# untitled.net
KiCad netlist of a schematic drawn in EAGLE
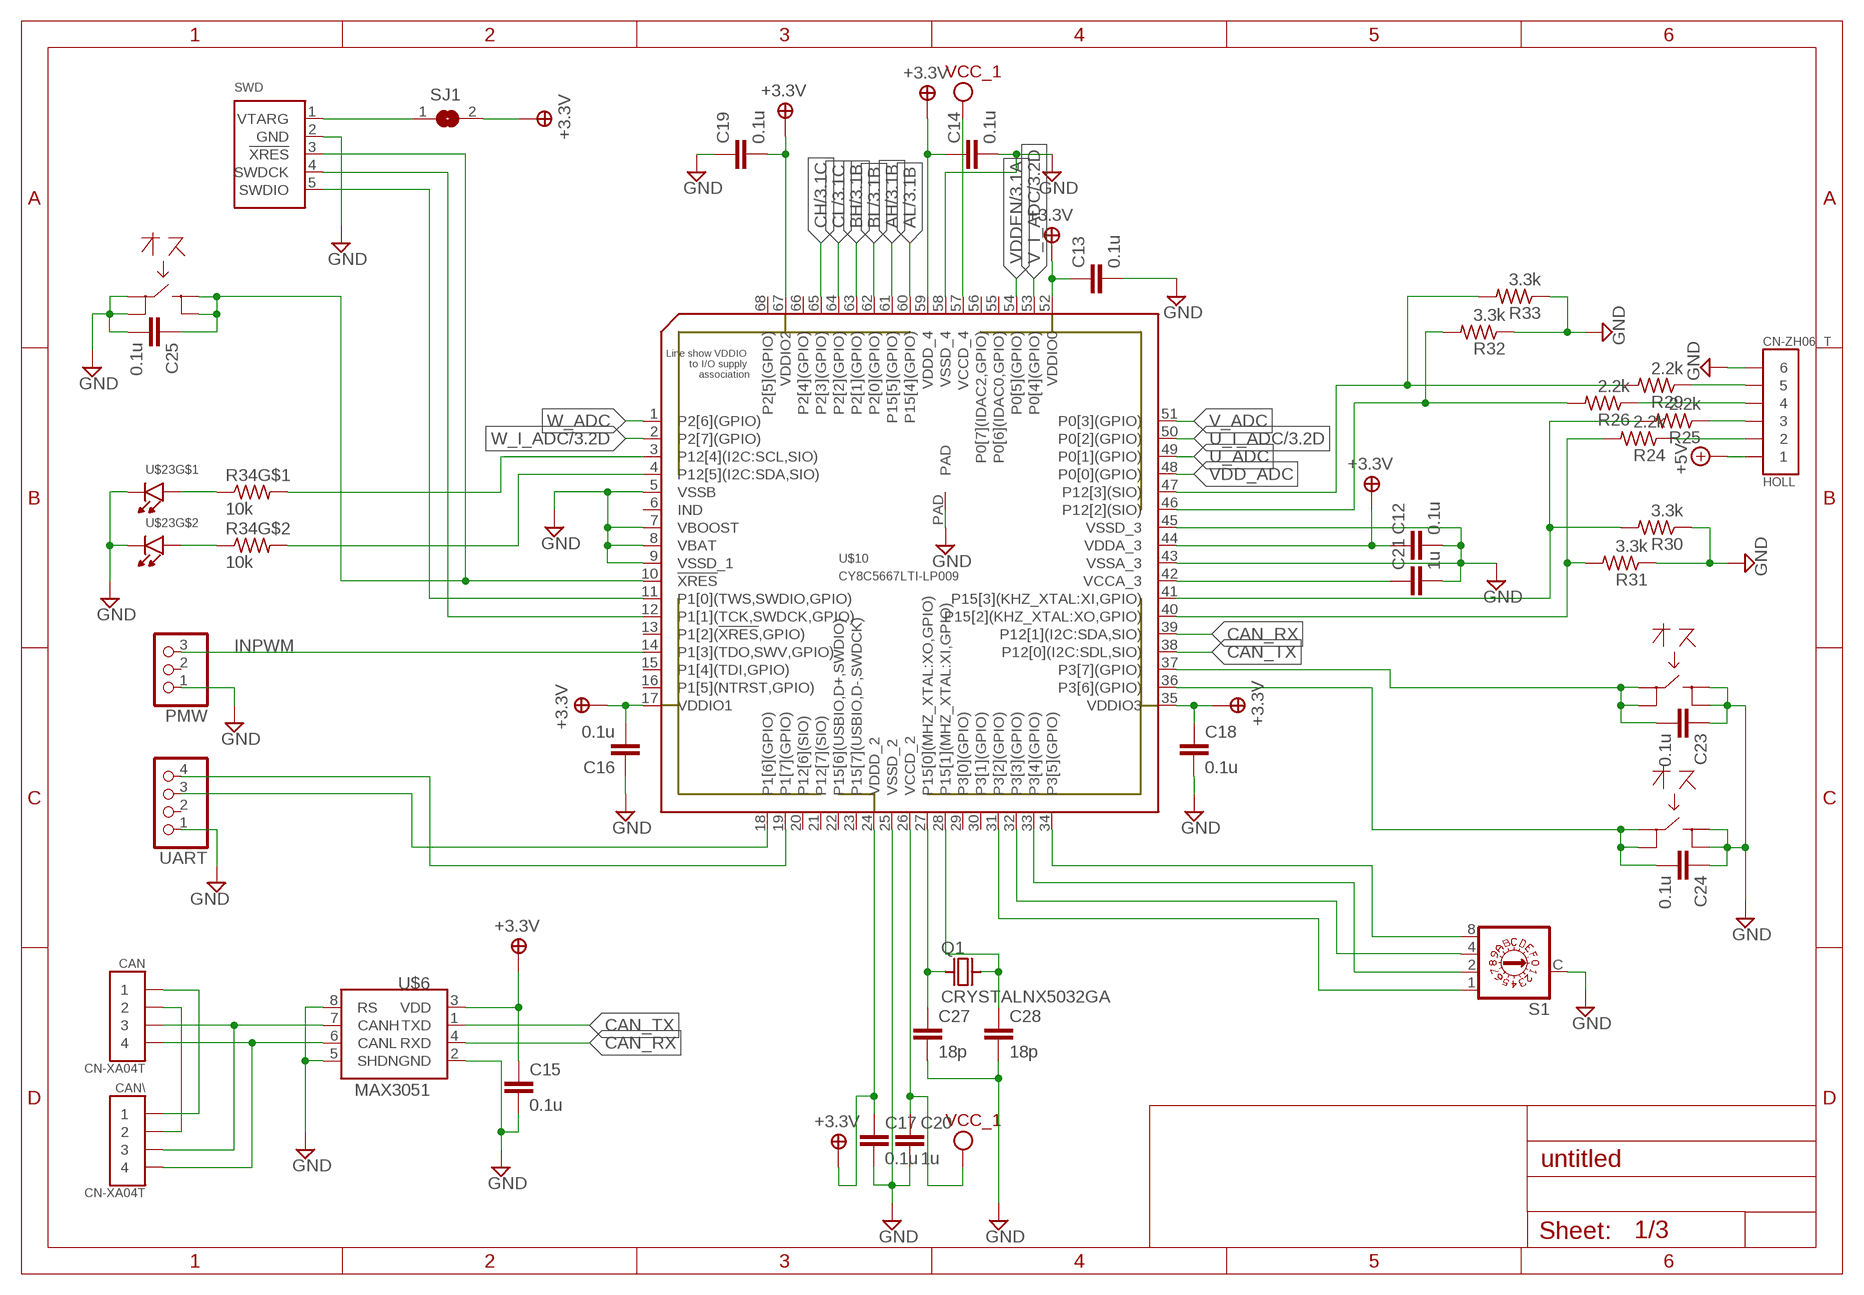
[diagram p0: schematic, sheet 1]
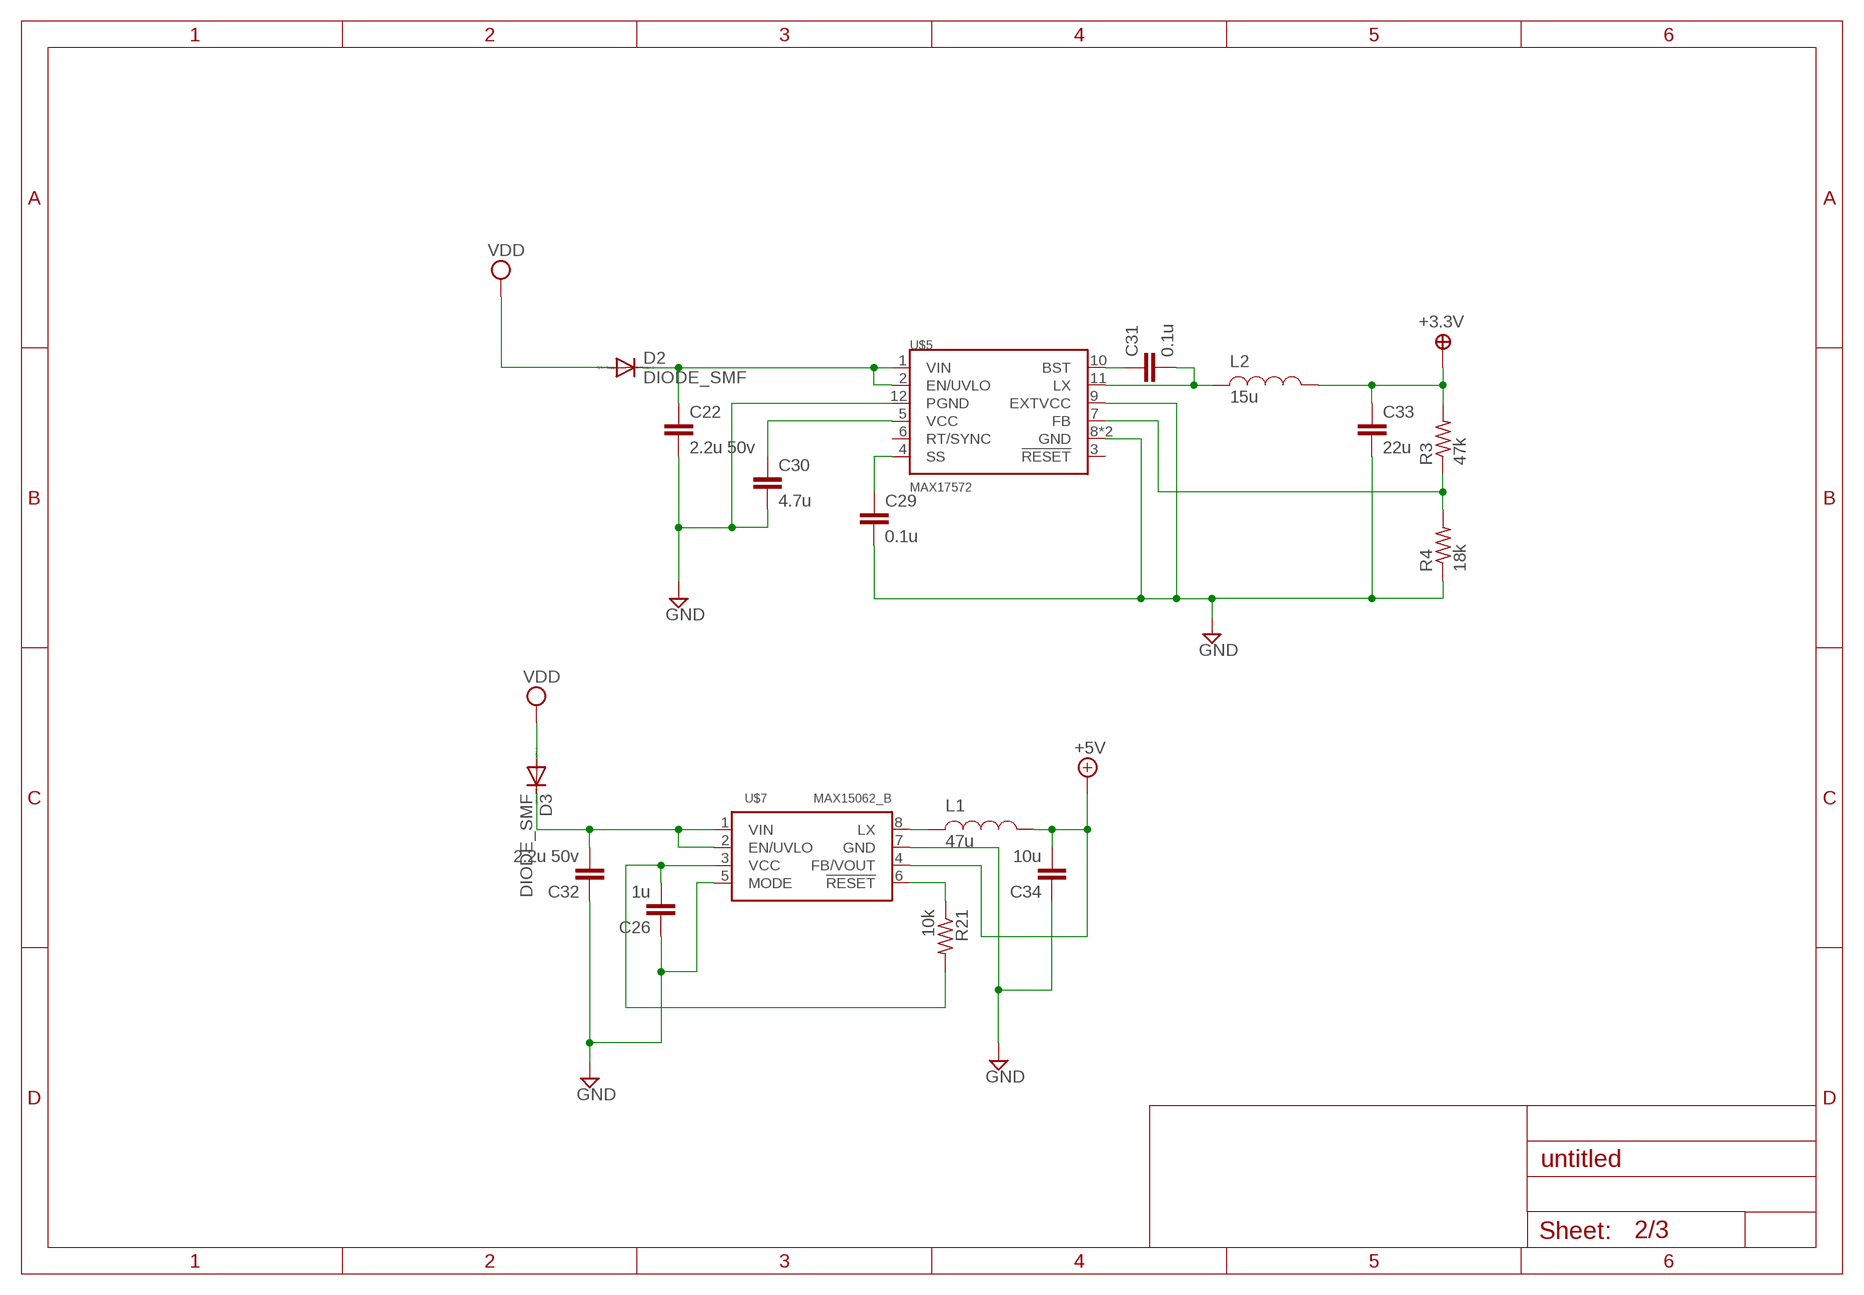
[diagram p1: schematic, sheet 2]
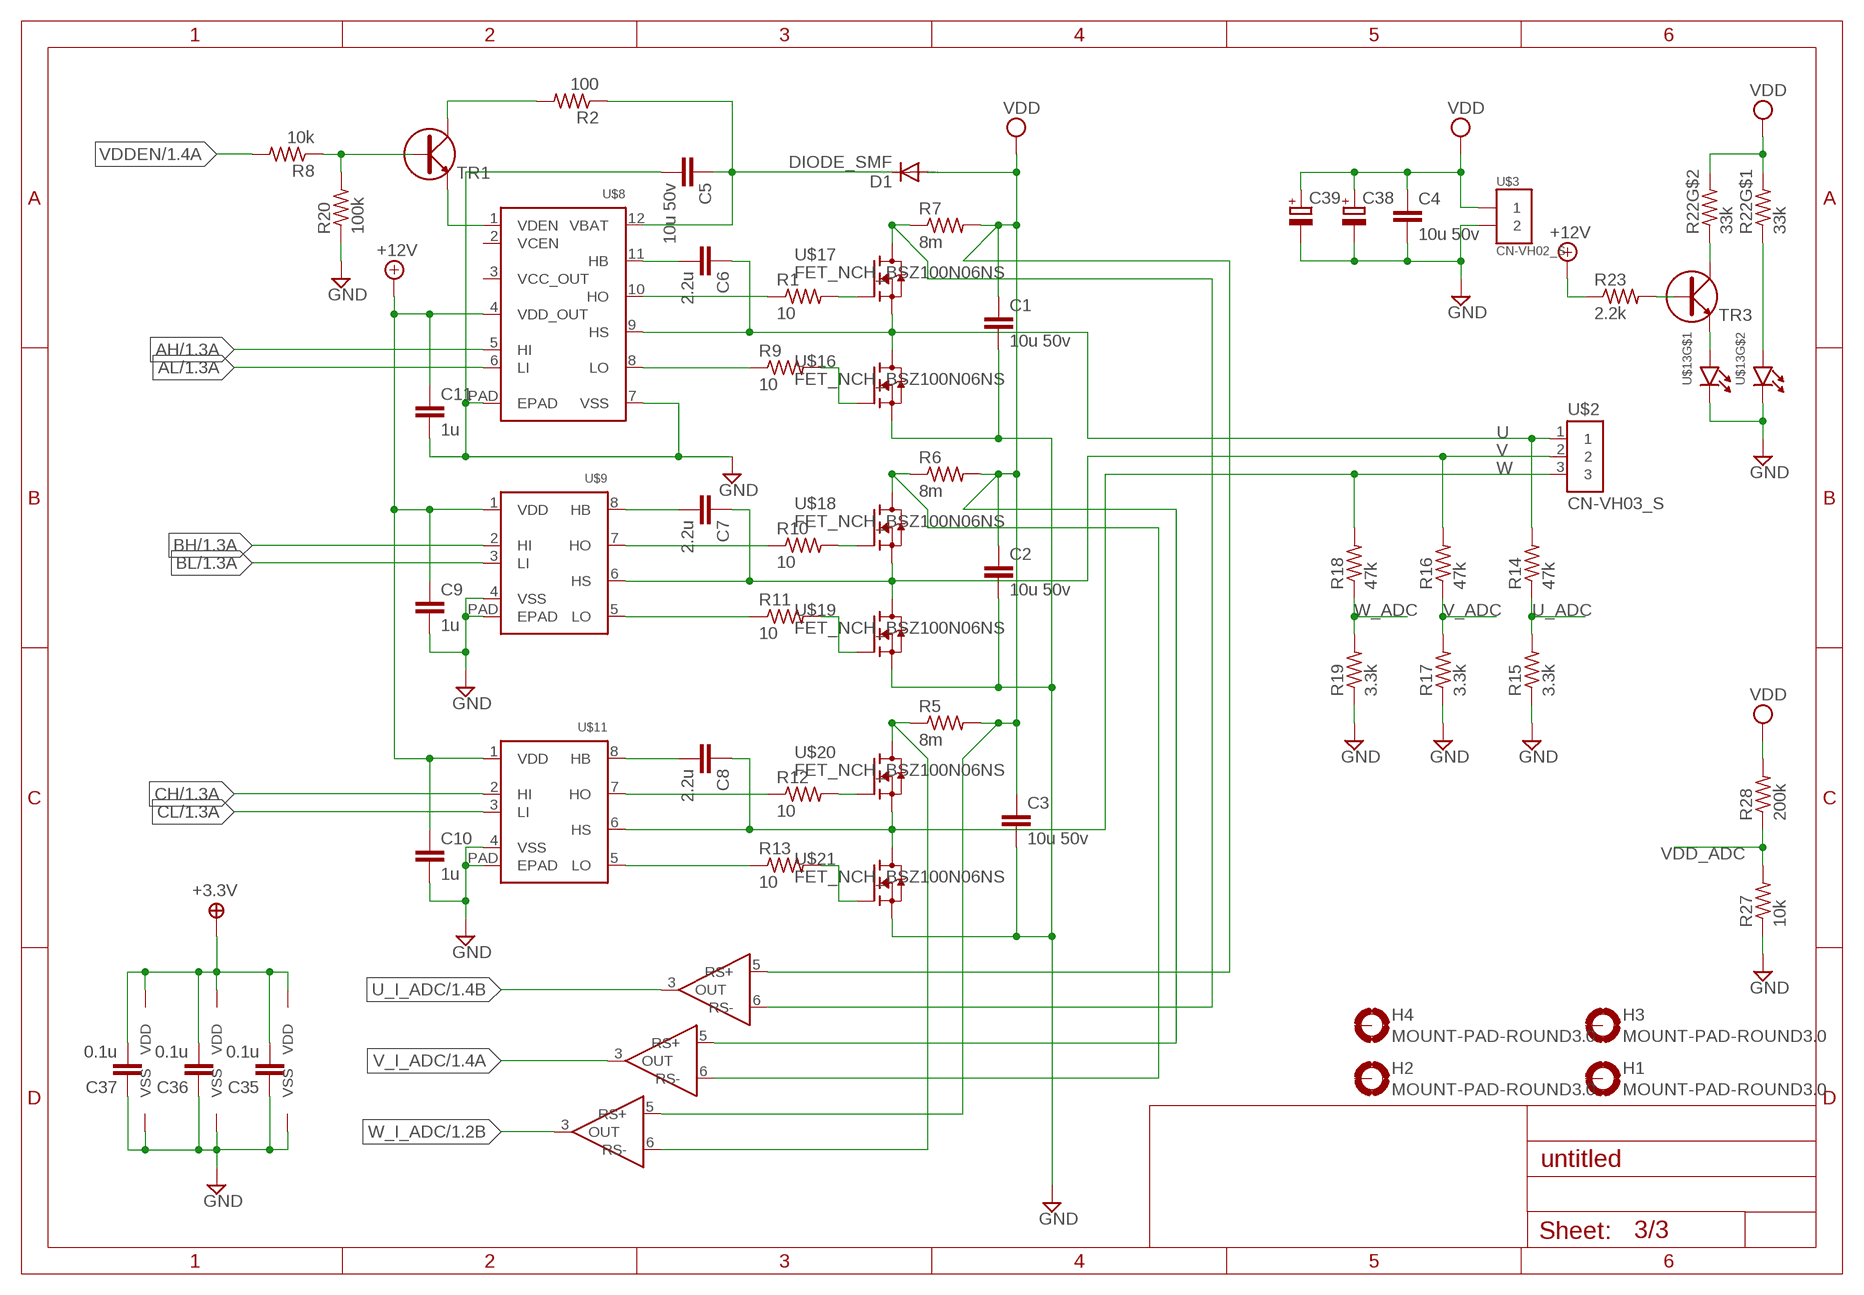
[diagram p2: schematic, sheet 3]

(export (version "E")
  (design (tool "Eeschema 10.0.6"))
  (components
    (comp (ref "C1")
      (value "10u 50v")
      (footprint "eagle-import:C3216")
      (libsource (lib "eagle-import") (part "CAPACITOR_3216M"))
    )
    (comp (ref "C2")
      (value "10u 50v")
      (footprint "eagle-import:C3216")
      (libsource (lib "eagle-import") (part "CAPACITOR_3216M"))
    )
    (comp (ref "C3")
      (value "10u 50v")
      (footprint "eagle-import:C3216")
      (libsource (lib "eagle-import") (part "CAPACITOR_3216M"))
    )
    (comp (ref "C4")
      (value "10u 50v")
      (footprint "eagle-import:C3216")
      (libsource (lib "eagle-import") (part "CAPACITOR_3216M"))
    )
    (comp (ref "C5")
      (value "10u 50v")
      (footprint "eagle-import:C3216")
      (libsource (lib "eagle-import") (part "CAPACITOR_3216M"))
    )
    (comp (ref "C6")
      (value "2.2u")
      (footprint "eagle-import:C1005")
      (libsource (lib "eagle-import") (part "CAPACITOR_1005M"))
    )
    (comp (ref "C7")
      (value "2.2u")
      (footprint "eagle-import:C1005")
      (libsource (lib "eagle-import") (part "CAPACITOR_1005M"))
    )
    (comp (ref "C8")
      (value "2.2u")
      (footprint "eagle-import:C1005")
      (libsource (lib "eagle-import") (part "CAPACITOR_1005M"))
    )
    (comp (ref "C9")
      (value "1u")
      (footprint "eagle-import:C1608")
      (libsource (lib "eagle-import") (part "CAPACITOR_1608M"))
    )
    (comp (ref "C10")
      (value "1u")
      (footprint "eagle-import:C1608")
      (libsource (lib "eagle-import") (part "CAPACITOR_1608M"))
    )
    (comp (ref "C11")
      (value "1u")
      (footprint "eagle-import:C1608")
      (libsource (lib "eagle-import") (part "CAPACITOR_1608M"))
    )
    (comp (ref "C35")
      (value "0.1u")
      (footprint "eagle-import:C1005")
      (libsource (lib "eagle-import") (part "CAPACITOR_1005M"))
    )
    (comp (ref "C36")
      (value "0.1u")
      (footprint "eagle-import:C1005")
      (libsource (lib "eagle-import") (part "CAPACITOR_1005M"))
    )
    (comp (ref "C37")
      (value "0.1u")
      (footprint "eagle-import:C1005")
      (libsource (lib "eagle-import") (part "CAPACITOR_1005M"))
    )
    (comp (ref "C38")
      (value "CPOL-EUG")
      (footprint "eagle-import:PANASONIC_G")
      (libsource (lib "eagle-import") (part "CPOL-EUG"))
    )
    (comp (ref "C39")
      (value "CPOL-EUE5-13")
      (footprint "eagle-import:E5-13")
      (libsource (lib "eagle-import") (part "CPOL-EUE5-13"))
    )
    (comp (ref "D1")
      (value "DIODE_SMF")
      (footprint "eagle-import:DO-219AB(SMF)")
      (libsource (lib "eagle-import") (part "DIODE_SMF"))
    )
    (comp (ref "H1")
      (value "MOUNT-PAD-ROUND3.0")
      (footprint "eagle-import:3,0-PAD")
      (libsource (lib "eagle-import") (part "MOUNT-PAD-ROUND3.0"))
    )
    (comp (ref "H2")
      (value "MOUNT-PAD-ROUND3.0")
      (footprint "eagle-import:3,0-PAD")
      (libsource (lib "eagle-import") (part "MOUNT-PAD-ROUND3.0"))
    )
    (comp (ref "H3")
      (value "MOUNT-PAD-ROUND3.0")
      (footprint "eagle-import:3,0-PAD")
      (libsource (lib "eagle-import") (part "MOUNT-PAD-ROUND3.0"))
    )
    (comp (ref "H4")
      (value "MOUNT-PAD-ROUND3.0")
      (footprint "eagle-import:3,0-PAD")
      (libsource (lib "eagle-import") (part "MOUNT-PAD-ROUND3.0"))
    )
    (comp (ref "R1")
      (value "10")
      (footprint "eagle-import:R1608")
      (libsource (lib "eagle-import") (part "R_1608"))
    )
    (comp (ref "R2")
      (value "100")
      (footprint "eagle-import:R1005")
      (libsource (lib "eagle-import") (part "R_1005"))
    )
    (comp (ref "R5")
      (value "8m")
      (footprint "eagle-import:R3216")
      (libsource (lib "eagle-import") (part "R_3216"))
    )
    (comp (ref "R6")
      (value "8m")
      (footprint "eagle-import:R3216")
      (libsource (lib "eagle-import") (part "R_3216"))
    )
    (comp (ref "R7")
      (value "8m")
      (footprint "eagle-import:R3216")
      (libsource (lib "eagle-import") (part "R_3216"))
    )
    (comp (ref "R8")
      (value "10k")
      (footprint "eagle-import:R1005")
      (libsource (lib "eagle-import") (part "R_1005"))
    )
    (comp (ref "R9")
      (value "10")
      (footprint "eagle-import:R1608")
      (libsource (lib "eagle-import") (part "R_1608"))
    )
    (comp (ref "R10")
      (value "10")
      (footprint "eagle-import:R1608")
      (libsource (lib "eagle-import") (part "R_1608"))
    )
    (comp (ref "R11")
      (value "10")
      (footprint "eagle-import:R1608")
      (libsource (lib "eagle-import") (part "R_1608"))
    )
    (comp (ref "R12")
      (value "10")
      (footprint "eagle-import:R1608")
      (libsource (lib "eagle-import") (part "R_1608"))
    )
    (comp (ref "R13")
      (value "10")
      (footprint "eagle-import:R1608")
      (libsource (lib "eagle-import") (part "R_1608"))
    )
    (comp (ref "R14")
      (value "47k")
      (footprint "eagle-import:R1005")
      (libsource (lib "eagle-import") (part "R_1005"))
    )
    (comp (ref "R15")
      (value "3.3k")
      (footprint "eagle-import:R1005")
      (libsource (lib "eagle-import") (part "R_1005"))
    )
    (comp (ref "R16")
      (value "47k")
      (footprint "eagle-import:R1005")
      (libsource (lib "eagle-import") (part "R_1005"))
    )
    (comp (ref "R17")
      (value "3.3k")
      (footprint "eagle-import:R1005")
      (libsource (lib "eagle-import") (part "R_1005"))
    )
    (comp (ref "R18")
      (value "47k")
      (footprint "eagle-import:R1005")
      (libsource (lib "eagle-import") (part "R_1005"))
    )
    (comp (ref "R19")
      (value "3.3k")
      (footprint "eagle-import:R1005")
      (libsource (lib "eagle-import") (part "R_1005"))
    )
    (comp (ref "R20")
      (value "100k")
      (footprint "eagle-import:R1005")
      (libsource (lib "eagle-import") (part "R_1005"))
    )
    (comp (ref "R22")
      (value "33k")
      (footprint "eagle-import:R1005_2")
      (libsource (lib "eagle-import") (part "R2_0402"))
    )
    (comp (ref "R23")
      (value "2.2k")
      (footprint "eagle-import:R1005")
      (libsource (lib "eagle-import") (part "R_1005"))
    )
    (comp (ref "R27")
      (value "10k")
      (footprint "eagle-import:R1005")
      (libsource (lib "eagle-import") (part "R_1005"))
    )
    (comp (ref "R28")
      (value "200k")
      (footprint "eagle-import:R1005")
      (libsource (lib "eagle-import") (part "R_1005"))
    )
    (comp (ref "TR1")
      (value "TR_NTR")
      (footprint "eagle-import:SOT-23-3")
      (libsource (lib "eagle-import") (part "TR_NTR"))
    )
    (comp (ref "TR3")
      (value "TR_NTR")
      (footprint "eagle-import:SOT-23-3")
      (libsource (lib "eagle-import") (part "TR_NTR"))
    )
    (comp (ref "U$2")
      (value "CN-VH03_S")
      (footprint "eagle-import:VH03-S")
      (libsource (lib "eagle-import") (part "CN-VH03_S"))
    )
    (comp (ref "U$3")
      (value "CN-VH02_S")
      (footprint "eagle-import:VH02-S")
      (libsource (lib "eagle-import") (part "CN-VH02_S"))
    )
    (comp (ref "U$8")
      (value "HIP2104")
      (footprint "eagle-import:DFN_4X4_12LD")
      (libsource (lib "eagle-import") (part "HIP2104"))
    )
    (comp (ref "U$9")
      (value "HIP2103")
      (footprint "eagle-import:DFN_3X3_8L")
      (libsource (lib "eagle-import") (part "HIP2103"))
    )
    (comp (ref "U$11")
      (value "HIP2103")
      (footprint "eagle-import:DFN_3X3_8L")
      (libsource (lib "eagle-import") (part "HIP2103"))
    )
    (comp (ref "U$13")
      (value "LED2_SML522")
      (footprint "eagle-import:LED1315")
      (libsource (lib "eagle-import") (part "LED2_SML522"))
    )
    (comp (ref "U$14")
      (value "MAX40010")
      (footprint "eagle-import:SOT-23-6")
      (libsource (lib "eagle-import") (part "MAX40010"))
    )
    (comp (ref "U$15")
      (value "MAX40010")
      (footprint "eagle-import:SOT-23-6")
      (libsource (lib "eagle-import") (part "MAX40010"))
    )
    (comp (ref "U$16")
      (value "FET_NCH_BSZ100N06NS")
      (footprint "eagle-import:TSDSON-8")
      (libsource (lib "eagle-import") (part "FET_NCH_BSZ100N06NS"))
    )
    (comp (ref "U$17")
      (value "FET_NCH_BSZ100N06NS")
      (footprint "eagle-import:TSDSON-8")
      (libsource (lib "eagle-import") (part "FET_NCH_BSZ100N06NS"))
    )
    (comp (ref "U$18")
      (value "FET_NCH_BSZ100N06NS")
      (footprint "eagle-import:TSDSON-8")
      (libsource (lib "eagle-import") (part "FET_NCH_BSZ100N06NS"))
    )
    (comp (ref "U$19")
      (value "FET_NCH_BSZ100N06NS")
      (footprint "eagle-import:TSDSON-8")
      (libsource (lib "eagle-import") (part "FET_NCH_BSZ100N06NS"))
    )
    (comp (ref "U$20")
      (value "FET_NCH_BSZ100N06NS")
      (footprint "eagle-import:TSDSON-8")
      (libsource (lib "eagle-import") (part "FET_NCH_BSZ100N06NS"))
    )
    (comp (ref "U$21")
      (value "FET_NCH_BSZ100N06NS")
      (footprint "eagle-import:TSDSON-8")
      (libsource (lib "eagle-import") (part "FET_NCH_BSZ100N06NS"))
    )
    (comp (ref "U$22")
      (value "MAX40010")
      (footprint "eagle-import:SOT-23-6")
      (libsource (lib "eagle-import") (part "MAX40010"))
    )
    (comp (ref "C22")
      (value "2.2u 50v")
      (footprint "eagle-import:C3216")
      (libsource (lib "eagle-import") (part "CAPACITOR_3216M"))
    )
    (comp (ref "C26")
      (value "1u")
      (footprint "eagle-import:C1608")
      (libsource (lib "eagle-import") (part "CAPACITOR_1608M"))
    )
    (comp (ref "C29")
      (value "0.1u")
      (footprint "eagle-import:C1005")
      (libsource (lib "eagle-import") (part "CAPACITOR_1005M"))
    )
    (comp (ref "C30")
      (value "4.7u")
      (footprint "eagle-import:C2012")
      (libsource (lib "eagle-import") (part "CAPACITOR_2012M"))
    )
    (comp (ref "C31")
      (value "0.1u")
      (footprint "eagle-import:C1005")
      (libsource (lib "eagle-import") (part "CAPACITOR_1005M"))
    )
    (comp (ref "C32")
      (value "2.2u 50v")
      (footprint "eagle-import:C3216")
      (libsource (lib "eagle-import") (part "CAPACITOR_3216M"))
    )
    (comp (ref "C33")
      (value "22u")
      (footprint "eagle-import:C3216")
      (libsource (lib "eagle-import") (part "CAPACITOR_3216M"))
    )
    (comp (ref "C34")
      (value "10u")
      (footprint "eagle-import:C1608")
      (libsource (lib "eagle-import") (part "CAPACITOR_1608M"))
    )
    (comp (ref "D2")
      (value "DIODE_SMF")
      (footprint "eagle-import:DO-219AB(SMF)")
      (libsource (lib "eagle-import") (part "DIODE_SMF"))
    )
    (comp (ref "D3")
      (value "DIODE_SMF")
      (footprint "eagle-import:DO-219AB(SMF)")
      (libsource (lib "eagle-import") (part "DIODE_SMF"))
    )
    (comp (ref "L1")
      (value "47u")
      (footprint "eagle-import:L2518")
      (libsource (lib "eagle-import") (part "INDUCTOR_BRC2518"))
    )
    (comp (ref "L2")
      (value "15u")
      (footprint "eagle-import:SRN4018")
      (libsource (lib "eagle-import") (part "INDUCTOR_150M"))
    )
    (comp (ref "R3")
      (value "47k")
      (footprint "eagle-import:R1005")
      (libsource (lib "eagle-import") (part "R_1005"))
    )
    (comp (ref "R4")
      (value "18k")
      (footprint "eagle-import:R1005")
      (libsource (lib "eagle-import") (part "R_1005"))
    )
    (comp (ref "R21")
      (value "10k")
      (footprint "eagle-import:R1005")
      (libsource (lib "eagle-import") (part "R_1005"))
    )
    (comp (ref "U$5")
      (value "MAX17572")
      (footprint "eagle-import:TDFN12-3X3")
      (libsource (lib "eagle-import") (part "MAX17572"))
    )
    (comp (ref "U$7")
      (value "MAX15062_B")
      (footprint "eagle-import:TDFN08_2X2(NO_BOTTOM)")
      (libsource (lib "eagle-import") (part "MAX15062_A"))
    )
    (comp (ref "C12")
      (value "0.1u")
      (footprint "eagle-import:C1005")
      (libsource (lib "eagle-import") (part "CAPACITOR_1005M"))
    )
    (comp (ref "C13")
      (value "0.1u")
      (footprint "eagle-import:C1005")
      (libsource (lib "eagle-import") (part "CAPACITOR_1005M"))
    )
    (comp (ref "C14")
      (value "0.1u")
      (footprint "eagle-import:C1005")
      (libsource (lib "eagle-import") (part "CAPACITOR_1005M"))
    )
    (comp (ref "C15")
      (value "0.1u")
      (footprint "eagle-import:C1005")
      (libsource (lib "eagle-import") (part "CAPACITOR_1005M"))
    )
    (comp (ref "C16")
      (value "0.1u")
      (footprint "eagle-import:C1005")
      (libsource (lib "eagle-import") (part "CAPACITOR_1005M"))
    )
    (comp (ref "C17")
      (value "0.1u")
      (footprint "eagle-import:C1005")
      (libsource (lib "eagle-import") (part "CAPACITOR_1005M"))
    )
    (comp (ref "C18")
      (value "0.1u")
      (footprint "eagle-import:C1005")
      (libsource (lib "eagle-import") (part "CAPACITOR_1005M"))
    )
    (comp (ref "C19")
      (value "0.1u")
      (footprint "eagle-import:C1005")
      (libsource (lib "eagle-import") (part "CAPACITOR_1005M"))
    )
    (comp (ref "C20")
      (value "1u")
      (footprint "eagle-import:C1608")
      (libsource (lib "eagle-import") (part "CAPACITOR_1608M"))
    )
    (comp (ref "C21")
      (value "1u")
      (footprint "eagle-import:C1608")
      (libsource (lib "eagle-import") (part "CAPACITOR_1608M"))
    )
    (comp (ref "C23")
      (value "0.1u")
      (footprint "eagle-import:C1005")
      (libsource (lib "eagle-import") (part "CAPACITOR_1005M"))
    )
    (comp (ref "C24")
      (value "0.1u")
      (footprint "eagle-import:C1005")
      (libsource (lib "eagle-import") (part "CAPACITOR_1005M"))
    )
    (comp (ref "C25")
      (value "0.1u")
      (footprint "eagle-import:C1005")
      (libsource (lib "eagle-import") (part "CAPACITOR_1005M"))
    )
    (comp (ref "C27")
      (value "18p")
      (footprint "eagle-import:C1608")
      (libsource (lib "eagle-import") (part "CAPACITOR_1608M"))
    )
    (comp (ref "C28")
      (value "18p")
      (footprint "eagle-import:C1608")
      (libsource (lib "eagle-import") (part "CAPACITOR_1608M"))
    )
    (comp (ref "CAN")
      (value "CN-XA04T")
      (footprint "eagle-import:XA04")
      (libsource (lib "eagle-import") (part "CN-XA04T"))
    )
    (comp (ref "CAN\\")
      (value "CN-XA04T")
      (footprint "eagle-import:XA04")
      (libsource (lib "eagle-import") (part "CN-XA04T"))
    )
    (comp (ref "HOLL")
      (value "CN-ZH06_T")
      (footprint "eagle-import:ZH06")
      (libsource (lib "eagle-import") (part "CN-ZH06_T"))
    )
    (comp (ref "PMW")
      (value "PINHD-1X03_2.54-S")
      (footprint "eagle-import:1X03-S")
      (libsource (lib "eagle-import") (part "PINHD-1X03_2.54-S"))
    )
    (comp (ref "Q1")
      (value "CRYSTALNX5032GA")
      (footprint "eagle-import:NX5032GA")
      (libsource (lib "eagle-import") (part "CRYSTALNX5032GA"))
    )
    (comp (ref "R24")
      (value "2.2k")
      (footprint "eagle-import:R1005")
      (libsource (lib "eagle-import") (part "R_1005"))
    )
    (comp (ref "R25")
      (value "2.2k")
      (footprint "eagle-import:R1005")
      (libsource (lib "eagle-import") (part "R_1005"))
    )
    (comp (ref "R26")
      (value "2.2k")
      (footprint "eagle-import:R1005")
      (libsource (lib "eagle-import") (part "R_1005"))
    )
    (comp (ref "R29")
      (value "2.2k")
      (footprint "eagle-import:R1005")
      (libsource (lib "eagle-import") (part "R_1005"))
    )
    (comp (ref "R30")
      (value "3.3k")
      (footprint "eagle-import:R1005")
      (libsource (lib "eagle-import") (part "R_1005"))
    )
    (comp (ref "R31")
      (value "3.3k")
      (footprint "eagle-import:R1005")
      (libsource (lib "eagle-import") (part "R_1005"))
    )
    (comp (ref "R32")
      (value "3.3k")
      (footprint "eagle-import:R1005")
      (libsource (lib "eagle-import") (part "R_1005"))
    )
    (comp (ref "R33")
      (value "3.3k")
      (footprint "eagle-import:R1005")
      (libsource (lib "eagle-import") (part "R_1005"))
    )
    (comp (ref "R34")
      (value "10k")
      (footprint "eagle-import:R1005_2")
      (libsource (lib "eagle-import") (part "R2_0402"))
    )
    (comp (ref "RESET")
      (value "SWITCH_4PALPS")
      (footprint "eagle-import:SKRP")
      (libsource (lib "eagle-import") (part "SWITCH_4PALPS"))
    )
    (comp (ref "S1")
      (value "P103_AKI")
      (footprint "eagle-import:SW_ROT_5")
      (libsource (lib "eagle-import") (part "P103_AKI"))
    )
    (comp (ref "SJ1") (value "SJ") (footprint "eagle-import:SJ") (libsource (lib "eagle-import") (part "SJ")))
    (comp (ref "SWD")
      (value "WRITE-FOR-PSOC3/4/5LP_ZH")
      (footprint "eagle-import:ZH05")
      (libsource (lib "eagle-import") (part "WRITE-FOR-PSOC3/4/5LP_ZH"))
    )
    (comp (ref "U$6")
      (value "MAX3051")
      (footprint "eagle-import:SOIC8")
      (libsource (lib "eagle-import") (part "MAX3051"))
    )
    (comp (ref "U$10")
      (value "CY8C5667LTI-LP009")
      (footprint "eagle-import:QFN68_8X8")
      (libsource (lib "eagle-import") (part "CY8C58LP_68"))
    )
    (comp (ref "U$23")
      (value "LED2_SML522")
      (footprint "eagle-import:LED1315")
      (libsource (lib "eagle-import") (part "LED2_SML522"))
    )
    (comp (ref "UART")
      (value "PINHD-1X04_2.54-S")
      (footprint "eagle-import:1X04-S")
      (libsource (lib "eagle-import") (part "PINHD-1X04_2.54-S"))
    )
    (comp (ref "USER1")
      (value "SWITCH_4PALPS")
      (footprint "eagle-import:SKRP")
      (libsource (lib "eagle-import") (part "SWITCH_4PALPS"))
    )
    (comp (ref "USER2")
      (value "SWITCH_4PALPS")
      (footprint "eagle-import:SKRP")
      (libsource (lib "eagle-import") (part "SWITCH_4PALPS"))
    )
  )
  (nets
    (net (code "1") (name "+5V") (class "Default")
      (node (ref "C34") (pin "2") (pinfunction "2_2") (pintype "passive"))
      (node (ref "HOLL") (pin "1") (pinfunction "1_1") (pintype "bidirectional"))
      (node (ref "L1") (pin "P$2") (pinfunction "P$2_P$2") (pintype "bidirectional"))
      (node (ref "U$7") (pin "4") (pinfunction "FB/VOUT_4") (pintype "bidirectional"))
    )
    (net (code "2") (name "+12V") (class "Default")
      (node (ref "C10") (pin "1") (pinfunction "1_1") (pintype "passive"))
      (node (ref "C11") (pin "1") (pinfunction "1_1") (pintype "passive"))
      (node (ref "C9") (pin "1") (pinfunction "1_1") (pintype "passive"))
      (node (ref "R23") (pin "1") (pinfunction "1_1") (pintype "passive"))
      (node (ref "U$11") (pin "1") (pinfunction "VDD_1") (pintype "bidirectional"))
      (node (ref "U$8") (pin "4") (pinfunction "VDD_OUT_4") (pintype "bidirectional"))
      (node (ref "U$9") (pin "1") (pinfunction "VDD_1") (pintype "bidirectional"))
    )
    (net (code "3") (name "3.3V") (class "Default")
      (node (ref "C12") (pin "1") (pinfunction "1_1") (pintype "passive"))
      (node (ref "C13") (pin "1") (pinfunction "1_1") (pintype "passive"))
      (node (ref "C14") (pin "1") (pinfunction "1_1") (pintype "passive"))
      (node (ref "C15") (pin "1") (pinfunction "1_1") (pintype "passive"))
      (node (ref "C16") (pin "2") (pinfunction "2_2") (pintype "passive"))
      (node (ref "C17") (pin "1") (pinfunction "1_1") (pintype "passive"))
      (node (ref "C18") (pin "1") (pinfunction "1_1") (pintype "passive"))
      (node (ref "C19") (pin "2") (pinfunction "2_2") (pintype "passive"))
      (node (ref "C33") (pin "1") (pinfunction "1_1") (pintype "passive"))
      (node (ref "C35") (pin "2") (pinfunction "2_2") (pintype "passive"))
      (node (ref "C36") (pin "2") (pinfunction "2_2") (pintype "passive"))
      (node (ref "C37") (pin "2") (pinfunction "2_2") (pintype "passive"))
      (node (ref "L2") (pin "P$2") (pinfunction "P$2_P$2") (pintype "bidirectional"))
      (node (ref "R3") (pin "2") (pinfunction "2_2") (pintype "passive"))
      (node (ref "SJ1") (pin "2") (pinfunction "2_2") (pintype "passive"))
      (node (ref "U$10") (pin "17") (pinfunction "VDDIO1_17") (pintype "bidirectional"))
      (node (ref "U$10") (pin "24") (pinfunction "VDDD_2_24") (pintype "bidirectional"))
      (node (ref "U$10") (pin "35") (pinfunction "VDDIO3_35") (pintype "bidirectional"))
      (node (ref "U$10") (pin "44") (pinfunction "VDDA_3_44") (pintype "bidirectional"))
      (node (ref "U$10") (pin "52") (pinfunction "VDDIO0_52") (pintype "bidirectional"))
      (node (ref "U$10") (pin "59") (pinfunction "VDDD_4_59") (pintype "bidirectional"))
      (node (ref "U$10") (pin "67") (pinfunction "VDDIO2_67") (pintype "bidirectional"))
      (node (ref "U$14") (pin "4") (pinfunction "VDD_4") (pintype "bidirectional"))
      (node (ref "U$15") (pin "4") (pinfunction "VDD_4") (pintype "bidirectional"))
      (node (ref "U$22") (pin "4") (pinfunction "VDD_4") (pintype "bidirectional"))
      (node (ref "U$6") (pin "3") (pinfunction "VDD_3") (pintype "bidirectional"))
    )
    (net (code "4") (name "AH") (class "Default")
      (node (ref "U$10") (pin "61") (pinfunction "P15[5](GPIO)_61") (pintype "bidirectional"))
      (node (ref "U$8") (pin "5") (pinfunction "HI_5") (pintype "bidirectional"))
    )
    (net (code "5") (name "AL") (class "Default")
      (node (ref "U$10") (pin "60") (pinfunction "P15[4](GPIO)_60") (pintype "bidirectional"))
      (node (ref "U$8") (pin "6") (pinfunction "LI_6") (pintype "bidirectional"))
    )
    (net (code "6") (name "BH") (class "Default")
      (node (ref "U$10") (pin "63") (pinfunction "P2[1](GPIO)_63") (pintype "bidirectional"))
      (node (ref "U$9") (pin "2") (pinfunction "HI_2") (pintype "bidirectional"))
    )
    (net (code "7") (name "BL") (class "Default")
      (node (ref "U$10") (pin "62") (pinfunction "P2[0](GPIO)_62") (pintype "bidirectional"))
      (node (ref "U$9") (pin "3") (pinfunction "LI_3") (pintype "bidirectional"))
    )
    (net (code "8") (name "CAN_RX") (class "Default")
      (node (ref "U$10") (pin "39") (pinfunction "P12[1](I2C:SDA,SIO)_39") (pintype "bidirectional"))
      (node (ref "U$6") (pin "4") (pinfunction "RXD_4") (pintype "bidirectional"))
    )
    (net (code "9") (name "CAN_TX") (class "Default")
      (node (ref "U$10") (pin "38") (pinfunction "P12[0](I2C:SDL,SIO)_38") (pintype "bidirectional"))
      (node (ref "U$6") (pin "1") (pinfunction "TXD_1") (pintype "bidirectional"))
    )
    (net (code "10") (name "CH") (class "Default")
      (node (ref "U$10") (pin "65") (pinfunction "P2[3](GPIO)_65") (pintype "bidirectional"))
      (node (ref "U$11") (pin "2") (pinfunction "HI_2") (pintype "bidirectional"))
    )
    (net (code "11") (name "CL") (class "Default")
      (node (ref "U$10") (pin "64") (pinfunction "P2[2](GPIO)_64") (pintype "bidirectional"))
      (node (ref "U$11") (pin "3") (pinfunction "LI_3") (pintype "bidirectional"))
    )
    (net (code "12") (name "GND") (class "Default")
      (node (ref "C1") (pin "2") (pinfunction "2_2") (pintype "passive"))
      (node (ref "C10") (pin "2") (pinfunction "2_2") (pintype "passive"))
      (node (ref "C11") (pin "2") (pinfunction "2_2") (pintype "passive"))
      (node (ref "C12") (pin "2") (pinfunction "2_2") (pintype "passive"))
      (node (ref "C13") (pin "2") (pinfunction "2_2") (pintype "passive"))
      (node (ref "C14") (pin "2") (pinfunction "2_2") (pintype "passive"))
      (node (ref "C15") (pin "2") (pinfunction "2_2") (pintype "passive"))
      (node (ref "C16") (pin "1") (pinfunction "1_1") (pintype "passive"))
      (node (ref "C17") (pin "2") (pinfunction "2_2") (pintype "passive"))
      (node (ref "C18") (pin "2") (pinfunction "2_2") (pintype "passive"))
      (node (ref "C19") (pin "1") (pinfunction "1_1") (pintype "passive"))
      (node (ref "C2") (pin "2") (pinfunction "2_2") (pintype "passive"))
      (node (ref "C20") (pin "2") (pinfunction "2_2") (pintype "passive"))
      (node (ref "C21") (pin "2") (pinfunction "2_2") (pintype "passive"))
      (node (ref "C22") (pin "2") (pinfunction "2_2") (pintype "passive"))
      (node (ref "C23") (pin "1") (pinfunction "1_1") (pintype "passive"))
      (node (ref "C24") (pin "1") (pinfunction "1_1") (pintype "passive"))
      (node (ref "C25") (pin "2") (pinfunction "2_2") (pintype "passive"))
      (node (ref "C26") (pin "1") (pinfunction "1_1") (pintype "passive"))
      (node (ref "C27") (pin "2") (pinfunction "2_2") (pintype "passive"))
      (node (ref "C28") (pin "2") (pinfunction "2_2") (pintype "passive"))
      (node (ref "C29") (pin "2") (pinfunction "2_2") (pintype "passive"))
      (node (ref "C3") (pin "2") (pinfunction "2_2") (pintype "passive"))
      (node (ref "C30") (pin "2") (pinfunction "2_2") (pintype "passive"))
      (node (ref "C32") (pin "1") (pinfunction "1_1") (pintype "passive"))
      (node (ref "C33") (pin "2") (pinfunction "2_2") (pintype "passive"))
      (node (ref "C34") (pin "1") (pinfunction "1_1") (pintype "passive"))
      (node (ref "C35") (pin "1") (pinfunction "1_1") (pintype "passive"))
      (node (ref "C36") (pin "1") (pinfunction "1_1") (pintype "passive"))
      (node (ref "C37") (pin "1") (pinfunction "1_1") (pintype "passive"))
      (node (ref "C38") (pin "-") (pinfunction "-_-") (pintype "passive"))
      (node (ref "C39") (pin "-") (pinfunction "-_-") (pintype "passive"))
      (node (ref "C4") (pin "2") (pinfunction "2_2") (pintype "passive"))
      (node (ref "C5") (pin "2") (pinfunction "2_2") (pintype "passive"))
      (node (ref "C9") (pin "2") (pinfunction "2_2") (pintype "passive"))
      (node (ref "HOLL") (pin "6") (pinfunction "6_6") (pintype "bidirectional"))
      (node (ref "PMW") (pin "1") (pinfunction "1_1") (pintype "passive"))
      (node (ref "R15") (pin "1") (pinfunction "1_1") (pintype "passive"))
      (node (ref "R17") (pin "1") (pinfunction "1_1") (pintype "passive"))
      (node (ref "R19") (pin "1") (pinfunction "1_1") (pintype "passive"))
      (node (ref "R20") (pin "1") (pinfunction "1_1") (pintype "passive"))
      (node (ref "R27") (pin "1") (pinfunction "1_1") (pintype "passive"))
      (node (ref "R30") (pin "1") (pinfunction "1_1") (pintype "passive"))
      (node (ref "R31") (pin "1") (pinfunction "1_1") (pintype "passive"))
      (node (ref "R32") (pin "1") (pinfunction "1_1") (pintype "passive"))
      (node (ref "R33") (pin "1") (pinfunction "1_1") (pintype "passive"))
      (node (ref "R4") (pin "1") (pinfunction "1_1") (pintype "passive"))
      (node (ref "RESET") (pin "1") (pinfunction "1_1") (pintype "bidirectional"))
      (node (ref "RESET") (pin "2") (pinfunction "2_2") (pintype "bidirectional"))
      (node (ref "S1") (pin "C") (pinfunction "C_C") (pintype "passive"))
      (node (ref "SWD") (pin "2") (pinfunction "GND_2") (pintype "bidirectional"))
      (node (ref "U$10") (pin "25") (pinfunction "VSSD_2_25") (pintype "bidirectional"))
      (node (ref "U$10") (pin "43") (pinfunction "VSSA_3_43") (pintype "bidirectional"))
      (node (ref "U$10") (pin "45") (pinfunction "VSSD_3_45") (pintype "bidirectional"))
      (node (ref "U$10") (pin "5") (pinfunction "VSSB_5") (pintype "bidirectional"))
      (node (ref "U$10") (pin "58") (pinfunction "VSSD_4_58") (pintype "bidirectional"))
      (node (ref "U$10") (pin "7") (pinfunction "VBOOST_7") (pintype "bidirectional"))
      (node (ref "U$10") (pin "8") (pinfunction "VBAT_8") (pintype "bidirectional"))
      (node (ref "U$10") (pin "9") (pinfunction "VSSD_1_9") (pintype "bidirectional"))
      (node (ref "U$10") (pin "PAD") (pinfunction "PAD_PAD") (pintype "bidirectional"))
      (node (ref "U$11") (pin "4") (pinfunction "VSS_4") (pintype "bidirectional"))
      (node (ref "U$11") (pin "PAD") (pinfunction "EPAD_PAD") (pintype "bidirectional"))
      (node (ref "U$13") (pin "2") (pinfunction "C_2") (pintype "bidirectional"))
      (node (ref "U$13") (pin "4") (pinfunction "C_4") (pintype "bidirectional"))
      (node (ref "U$14") (pin "2") (pinfunction "VSS_2") (pintype "bidirectional"))
      (node (ref "U$15") (pin "2") (pinfunction "VSS_2") (pintype "bidirectional"))
      (node (ref "U$16") (pin "1") (pinfunction "S_1") (pintype "bidirectional"))
      (node (ref "U$16") (pin "123") (pinfunction "S_123") (pintype "bidirectional"))
      (node (ref "U$16") (pin "2") (pinfunction "S_2") (pintype "bidirectional"))
      (node (ref "U$16") (pin "3") (pinfunction "S_3") (pintype "bidirectional"))
      (node (ref "U$19") (pin "1") (pinfunction "S_1") (pintype "bidirectional"))
      (node (ref "U$19") (pin "123") (pinfunction "S_123") (pintype "bidirectional"))
      (node (ref "U$19") (pin "2") (pinfunction "S_2") (pintype "bidirectional"))
      (node (ref "U$19") (pin "3") (pinfunction "S_3") (pintype "bidirectional"))
      (node (ref "U$21") (pin "1") (pinfunction "S_1") (pintype "bidirectional"))
      (node (ref "U$21") (pin "123") (pinfunction "S_123") (pintype "bidirectional"))
      (node (ref "U$21") (pin "2") (pinfunction "S_2") (pintype "bidirectional"))
      (node (ref "U$21") (pin "3") (pinfunction "S_3") (pintype "bidirectional"))
      (node (ref "U$22") (pin "2") (pinfunction "VSS_2") (pintype "bidirectional"))
      (node (ref "U$23") (pin "2") (pinfunction "C_2") (pintype "bidirectional"))
      (node (ref "U$23") (pin "4") (pinfunction "C_4") (pintype "bidirectional"))
      (node (ref "U$3") (pin "1") (pinfunction "2_1") (pintype "bidirectional"))
      (node (ref "U$5") (pin "12") (pinfunction "PGND_12") (pintype "bidirectional"))
      (node (ref "U$5") (pin "8") (pinfunction "GND_8") (pintype "bidirectional"))
      (node (ref "U$5") (pin "9") (pinfunction "EXTVCC_9") (pintype "bidirectional"))
      (node (ref "U$5") (pin "EPAD") (pinfunction "GND_EPAD") (pintype "bidirectional"))
      (node (ref "U$6") (pin "2") (pinfunction "GND_2") (pintype "bidirectional"))
      (node (ref "U$6") (pin "5") (pinfunction "SHDN_5") (pintype "bidirectional"))
      (node (ref "U$6") (pin "8") (pinfunction "RS_8") (pintype "bidirectional"))
      (node (ref "U$7") (pin "5") (pinfunction "MODE_5") (pintype "bidirectional"))
      (node (ref "U$7") (pin "7") (pinfunction "GND_7") (pintype "bidirectional"))
      (node (ref "U$8") (pin "7") (pinfunction "VSS_7") (pintype "bidirectional"))
      (node (ref "U$8") (pin "PAD") (pinfunction "EPAD_PAD") (pintype "bidirectional"))
      (node (ref "U$9") (pin "4") (pinfunction "VSS_4") (pintype "bidirectional"))
      (node (ref "U$9") (pin "PAD") (pinfunction "EPAD_PAD") (pintype "bidirectional"))
      (node (ref "UART") (pin "1") (pinfunction "1_1") (pintype "passive"))
      (node (ref "USER1") (pin "3") (pinfunction "3_3") (pintype "bidirectional"))
      (node (ref "USER1") (pin "4") (pinfunction "4_4") (pintype "bidirectional"))
      (node (ref "USER2") (pin "3") (pinfunction "3_3") (pintype "bidirectional"))
      (node (ref "USER2") (pin "4") (pinfunction "4_4") (pintype "bidirectional"))
    )
    (net (code "13") (name "INPWM") (class "Default")
      (node (ref "PMW") (pin "3") (pinfunction "3_3") (pintype "passive"))
      (node (ref "U$10") (pin "14") (pinfunction "P1[3](TDO,SWV,GPIO)_14") (pintype "bidirectional"))
    )
    (net (code "14") (name "Net-(CAN-1)") (class "Default")
      (node (ref "CAN") (pin "PIN1") (pinfunction "1_PIN1") (pintype "bidirectional"))
      (node (ref "CAN\\") (pin "PIN1") (pinfunction "1_PIN1") (pintype "bidirectional"))
    )
    (net (code "15") (name "Net-(CAN-2)") (class "Default")
      (node (ref "CAN") (pin "PIN2") (pinfunction "2_PIN2") (pintype "bidirectional"))
      (node (ref "CAN\\") (pin "PIN2") (pinfunction "2_PIN2") (pintype "bidirectional"))
    )
    (net (code "16") (name "Net-(CAN-3)") (class "Default")
      (node (ref "CAN") (pin "PIN3") (pinfunction "3_PIN3") (pintype "bidirectional"))
      (node (ref "CAN\\") (pin "PIN3") (pinfunction "3_PIN3") (pintype "bidirectional"))
      (node (ref "U$6") (pin "7") (pinfunction "CANH_7") (pintype "bidirectional"))
    )
    (net (code "17") (name "Net-(CAN-4)") (class "Default")
      (node (ref "CAN") (pin "PIN4") (pinfunction "4_PIN4") (pintype "bidirectional"))
      (node (ref "CAN\\") (pin "PIN4") (pinfunction "4_PIN4") (pintype "bidirectional"))
      (node (ref "U$6") (pin "6") (pinfunction "CANL_6") (pintype "bidirectional"))
    )
    (net (code "18") (name "Net-(HOLL-Pad2)") (class "Default")
      (node (ref "HOLL") (pin "2") (pinfunction "2_2") (pintype "bidirectional"))
      (node (ref "R24") (pin "1") (pinfunction "1_1") (pintype "passive"))
    )
    (net (code "19") (name "Net-(HOLL-Pad3)") (class "Default")
      (node (ref "HOLL") (pin "3") (pinfunction "3_3") (pintype "bidirectional"))
      (node (ref "R25") (pin "1") (pinfunction "1_1") (pintype "passive"))
    )
    (net (code "20") (name "Net-(HOLL-Pad4)") (class "Default")
      (node (ref "HOLL") (pin "4") (pinfunction "4_4") (pintype "bidirectional"))
      (node (ref "R26") (pin "1") (pinfunction "1_1") (pintype "passive"))
    )
    (net (code "21") (name "Net-(HOLL-Pad5)") (class "Default")
      (node (ref "HOLL") (pin "5") (pinfunction "5_5") (pintype "bidirectional"))
      (node (ref "R29") (pin "1") (pinfunction "1_1") (pintype "passive"))
    )
    (net (code "22") (name "Net-(R22A-1)") (class "Default")
      (node (ref "R22") (pin "A1") (pinfunction "1_A1") (pintype "passive"))
      (node (ref "U$13") (pin "3") (pinfunction "A_3") (pintype "bidirectional"))
    )
    (net (code "23") (name "Net-(R22B-1)") (class "Default")
      (node (ref "R22") (pin "B1") (pinfunction "1_B1") (pintype "passive"))
      (node (ref "TR3") (pin "3") (pinfunction "C_3") (pintype "bidirectional"))
    )
    (net (code "24") (name "Net-(R34A-1)") (class "Default")
      (node (ref "R34") (pin "A1") (pinfunction "1_A1") (pintype "passive"))
      (node (ref "U$23") (pin "1") (pinfunction "A_1") (pintype "bidirectional"))
    )
    (net (code "25") (name "Net-(R34A-2)") (class "Default")
      (node (ref "R34") (pin "A2") (pinfunction "2_A2") (pintype "passive"))
      (node (ref "U$10") (pin "3") (pinfunction "P12[4](I2C:SCL,SIO)_3") (pintype "bidirectional"))
    )
    (net (code "26") (name "Net-(R34B-1)") (class "Default")
      (node (ref "R34") (pin "B1") (pinfunction "1_B1") (pintype "passive"))
      (node (ref "U$23") (pin "3") (pinfunction "A_3") (pintype "bidirectional"))
    )
    (net (code "27") (name "Net-(R34B-2)") (class "Default")
      (node (ref "R34") (pin "B2") (pinfunction "2_B2") (pintype "passive"))
      (node (ref "U$10") (pin "4") (pinfunction "P12[5](I2C:SDA,SIO)_4") (pintype "bidirectional"))
    )
    (net (code "28") (name "Net-(SWD-SWDCK)") (class "Default")
      (node (ref "SWD") (pin "4") (pinfunction "SWDCK_4") (pintype "bidirectional"))
      (node (ref "U$10") (pin "12") (pinfunction "P1[1](TCK,SWDCK,GPIO)_12") (pintype "bidirectional"))
    )
    (net (code "29") (name "Net-(SWD-SWDIO)") (class "Default")
      (node (ref "SWD") (pin "5") (pinfunction "SWDIO_5") (pintype "bidirectional"))
      (node (ref "U$10") (pin "11") (pinfunction "P1[0](TWS,SWDIO,GPIO)_11") (pintype "bidirectional"))
    )
    (net (code "30") (name "Net-(SWD-VTARG)") (class "Default")
      (node (ref "SJ1") (pin "1") (pinfunction "1_1") (pintype "passive"))
      (node (ref "SWD") (pin "1") (pinfunction "VTARG_1") (pintype "bidirectional"))
    )
    (net (code "31") (name "Net-(SWD-~{XRES})") (class "Default")
      (node (ref "C25") (pin "1") (pinfunction "1_1") (pintype "passive"))
      (node (ref "RESET") (pin "3") (pinfunction "3_3") (pintype "bidirectional"))
      (node (ref "RESET") (pin "4") (pinfunction "4_4") (pintype "bidirectional"))
      (node (ref "SWD") (pin "3") (pinfunction "~{XRES}_3") (pintype "bidirectional"))
      (node (ref "U$10") (pin "10") (pinfunction "~{XRES}_10") (pintype "bidirectional"))
    )
    (net (code "32") (name "Net-(TR1-B)") (class "Default")
      (node (ref "R20") (pin "2") (pinfunction "2_2") (pintype "passive"))
      (node (ref "R8") (pin "1") (pinfunction "1_1") (pintype "passive"))
      (node (ref "TR1") (pin "1") (pinfunction "B_1") (pintype "bidirectional"))
    )
    (net (code "33") (name "Net-(TR1-C)") (class "Default")
      (node (ref "R2") (pin "2") (pinfunction "2_2") (pintype "passive"))
      (node (ref "TR1") (pin "3") (pinfunction "C_3") (pintype "bidirectional"))
    )
    (net (code "34") (name "Net-(TR1-E)") (class "Default")
      (node (ref "TR1") (pin "2") (pinfunction "E_2") (pintype "bidirectional"))
      (node (ref "U$8") (pin "1") (pinfunction "VDEN_1") (pintype "bidirectional"))
    )
    (net (code "35") (name "Net-(TR3-B)") (class "Default")
      (node (ref "R23") (pin "2") (pinfunction "2_2") (pintype "passive"))
      (node (ref "TR3") (pin "1") (pinfunction "B_1") (pintype "bidirectional"))
    )
    (net (code "36") (name "Net-(TR3-E)") (class "Default")
      (node (ref "TR3") (pin "2") (pinfunction "E_2") (pintype "bidirectional"))
      (node (ref "U$13") (pin "1") (pinfunction "A_1") (pintype "bidirectional"))
    )
    (net (code "37") (name "Net-(U$5-BST)") (class "Default")
      (node (ref "C31") (pin "1") (pinfunction "1_1") (pintype "passive"))
      (node (ref "U$5") (pin "10") (pinfunction "BST_10") (pintype "bidirectional"))
    )
    (net (code "38") (name "Net-(U$5-EN{slash}UVLO)") (class "Default")
      (node (ref "C22") (pin "1") (pinfunction "1_1") (pintype "passive"))
      (node (ref "D2") (pin "C") (pinfunction "C_C") (pintype "passive"))
      (node (ref "U$5") (pin "1") (pinfunction "VIN_1") (pintype "bidirectional"))
      (node (ref "U$5") (pin "2") (pinfunction "EN/UVLO_2") (pintype "bidirectional"))
    )
    (net (code "39") (name "Net-(U$5-FB)") (class "Default")
      (node (ref "R3") (pin "1") (pinfunction "1_1") (pintype "passive"))
      (node (ref "R4") (pin "2") (pinfunction "2_2") (pintype "passive"))
      (node (ref "U$5") (pin "7") (pinfunction "FB_7") (pintype "bidirectional"))
    )
    (net (code "40") (name "Net-(U$5-LX)") (class "Default")
      (node (ref "C31") (pin "2") (pinfunction "2_2") (pintype "passive"))
      (node (ref "L2") (pin "P$1") (pinfunction "P$1_P$1") (pintype "bidirectional"))
      (node (ref "U$5") (pin "11") (pinfunction "LX_11") (pintype "bidirectional"))
    )
    (net (code "41") (name "Net-(U$5-SS)") (class "Default")
      (node (ref "C29") (pin "1") (pinfunction "1_1") (pintype "passive"))
      (node (ref "U$5") (pin "4") (pinfunction "SS_4") (pintype "bidirectional"))
    )
    (net (code "42") (name "Net-(U$5-VCC)") (class "Default")
      (node (ref "C30") (pin "1") (pinfunction "1_1") (pintype "passive"))
      (node (ref "U$5") (pin "5") (pinfunction "VCC_5") (pintype "bidirectional"))
    )
    (net (code "43") (name "Net-(U$7-EN{slash}UVLO)") (class "Default")
      (node (ref "C32") (pin "2") (pinfunction "2_2") (pintype "passive"))
      (node (ref "D3") (pin "C") (pinfunction "C_C") (pintype "passive"))
      (node (ref "U$7") (pin "1") (pinfunction "VIN_1") (pintype "bidirectional"))
      (node (ref "U$7") (pin "2") (pinfunction "EN/UVLO_2") (pintype "bidirectional"))
    )
    (net (code "44") (name "Net-(U$7-LX)") (class "Default")
      (node (ref "L1") (pin "P$1") (pinfunction "P$1_P$1") (pintype "bidirectional"))
      (node (ref "U$7") (pin "8") (pinfunction "LX_8") (pintype "bidirectional"))
    )
    (net (code "45") (name "Net-(U$7-VCC)") (class "Default")
      (node (ref "C26") (pin "2") (pinfunction "2_2") (pintype "passive"))
      (node (ref "R21") (pin "2") (pinfunction "2_2") (pintype "passive"))
      (node (ref "U$7") (pin "3") (pinfunction "VCC_3") (pintype "bidirectional"))
    )
    (net (code "46") (name "Net-(U$7-~{RESET})") (class "Default")
      (node (ref "R21") (pin "1") (pinfunction "1_1") (pintype "passive"))
      (node (ref "U$7") (pin "6") (pinfunction "~{RESET}_6") (pintype "bidirectional"))
    )
    (net (code "47") (name "Net-(U$8-HB)") (class "Default")
      (node (ref "C6") (pin "2") (pinfunction "2_2") (pintype "passive"))
      (node (ref "U$8") (pin "11") (pinfunction "HB_11") (pintype "bidirectional"))
    )
    (net (code "48") (name "Net-(U$8-HO)") (class "Default")
      (node (ref "R1") (pin "1") (pinfunction "1_1") (pintype "passive"))
      (node (ref "U$8") (pin "10") (pinfunction "HO_10") (pintype "bidirectional"))
    )
    (net (code "49") (name "Net-(U$8-LO)") (class "Default")
      (node (ref "R9") (pin "1") (pinfunction "1_1") (pintype "passive"))
      (node (ref "U$8") (pin "8") (pinfunction "LO_8") (pintype "bidirectional"))
    )
    (net (code "50") (name "Net-(U$8-VBAT)") (class "Default")
      (node (ref "C5") (pin "1") (pinfunction "1_1") (pintype "passive"))
      (node (ref "D1") (pin "C") (pinfunction "C_C") (pintype "passive"))
      (node (ref "R2") (pin "1") (pinfunction "1_1") (pintype "passive"))
      (node (ref "U$8") (pin "12") (pinfunction "VBAT_12") (pintype "bidirectional"))
    )
    (net (code "51") (name "Net-(U$9-HB)") (class "Default")
      (node (ref "C7") (pin "2") (pinfunction "2_2") (pintype "passive"))
      (node (ref "U$9") (pin "8") (pinfunction "HB_8") (pintype "bidirectional"))
    )
    (net (code "52") (name "Net-(U$9-HO)") (class "Default")
      (node (ref "R10") (pin "1") (pinfunction "1_1") (pintype "passive"))
      (node (ref "U$9") (pin "7") (pinfunction "HO_7") (pintype "bidirectional"))
    )
    (net (code "53") (name "Net-(U$9-LO)") (class "Default")
      (node (ref "R11") (pin "1") (pinfunction "1_1") (pintype "passive"))
      (node (ref "U$9") (pin "5") (pinfunction "LO_5") (pintype "bidirectional"))
    )
    (net (code "54") (name "Net-(U$10-P1[6](GPIO))") (class "Default")
      (node (ref "U$10") (pin "18") (pinfunction "P1[6](GPIO)_18") (pintype "bidirectional"))
      (node (ref "UART") (pin "3") (pinfunction "3_3") (pintype "passive"))
    )
    (net (code "55") (name "Net-(U$10-P1[7](GPIO))") (class "Default")
      (node (ref "U$10") (pin "19") (pinfunction "P1[7](GPIO)_19") (pintype "bidirectional"))
      (node (ref "UART") (pin "4") (pinfunction "4_4") (pintype "passive"))
    )
    (net (code "56") (name "Net-(U$10-P3[2](GPIO))") (class "Default")
      (node (ref "S1") (pin "1") (pinfunction "1_1") (pintype "passive"))
      (node (ref "U$10") (pin "31") (pinfunction "P3[2](GPIO)_31") (pintype "bidirectional"))
    )
    (net (code "57") (name "Net-(U$10-P3[3](GPIO))") (class "Default")
      (node (ref "S1") (pin "4") (pinfunction "4_4") (pintype "passive"))
      (node (ref "U$10") (pin "32") (pinfunction "P3[3](GPIO)_32") (pintype "bidirectional"))
    )
    (net (code "58") (name "Net-(U$10-P3[4](GPIO))") (class "Default")
      (node (ref "S1") (pin "2") (pinfunction "2_2") (pintype "passive"))
      (node (ref "U$10") (pin "33") (pinfunction "P3[4](GPIO)_33") (pintype "bidirectional"))
    )
    (net (code "59") (name "Net-(U$10-P3[5](GPIO))") (class "Default")
      (node (ref "S1") (pin "8") (pinfunction "8_8") (pintype "passive"))
      (node (ref "U$10") (pin "34") (pinfunction "P3[5](GPIO)_34") (pintype "bidirectional"))
    )
    (net (code "60") (name "Net-(U$10-P3[6](GPIO))") (class "Default")
      (node (ref "C24") (pin "2") (pinfunction "2_2") (pintype "passive"))
      (node (ref "U$10") (pin "36") (pinfunction "P3[6](GPIO)_36") (pintype "bidirectional"))
      (node (ref "USER2") (pin "1") (pinfunction "1_1") (pintype "bidirectional"))
      (node (ref "USER2") (pin "2") (pinfunction "2_2") (pintype "bidirectional"))
    )
    (net (code "61") (name "Net-(U$10-P3[7](GPIO))") (class "Default")
      (node (ref "C23") (pin "2") (pinfunction "2_2") (pintype "passive"))
      (node (ref "U$10") (pin "37") (pinfunction "P3[7](GPIO)_37") (pintype "bidirectional"))
      (node (ref "USER1") (pin "1") (pinfunction "1_1") (pintype "bidirectional"))
      (node (ref "USER1") (pin "2") (pinfunction "2_2") (pintype "bidirectional"))
    )
    (net (code "62") (name "Net-(U$10-P12[2](SIO))") (class "Default")
      (node (ref "R26") (pin "2") (pinfunction "2_2") (pintype "passive"))
      (node (ref "R32") (pin "2") (pinfunction "2_2") (pintype "passive"))
      (node (ref "U$10") (pin "46") (pinfunction "P12[2](SIO)_46") (pintype "bidirectional"))
    )
    (net (code "63") (name "Net-(U$10-P12[3](SIO))") (class "Default")
      (node (ref "R29") (pin "2") (pinfunction "2_2") (pintype "passive"))
      (node (ref "R33") (pin "2") (pinfunction "2_2") (pintype "passive"))
      (node (ref "U$10") (pin "47") (pinfunction "P12[3](SIO)_47") (pintype "bidirectional"))
    )
    (net (code "64") (name "Net-(U$10-P15[0](MHZ_XTAL:XO,GPIO))") (class "Default")
      (node (ref "C27") (pin "1") (pinfunction "1_1") (pintype "passive"))
      (node (ref "Q1") (pin "1") (pinfunction "1_1") (pintype "bidirectional"))
      (node (ref "U$10") (pin "27") (pinfunction "P15[0](MHZ_XTAL:XO,GPIO)_27") (pintype "bidirectional"))
    )
    (net (code "65") (name "Net-(U$10-P15[1](MHZ_XTAL:XI,GPIO))") (class "Default")
      (node (ref "C28") (pin "1") (pinfunction "1_1") (pintype "passive"))
      (node (ref "Q1") (pin "2") (pinfunction "2_2") (pintype "bidirectional"))
      (node (ref "U$10") (pin "28") (pinfunction "P15[1](MHZ_XTAL:XI,GPIO)_28") (pintype "bidirectional"))
    )
    (net (code "66") (name "Net-(U$10-P15[2](KHZ_XTAL:XO,GPIO))") (class "Default")
      (node (ref "R24") (pin "2") (pinfunction "2_2") (pintype "passive"))
      (node (ref "R31") (pin "2") (pinfunction "2_2") (pintype "passive"))
      (node (ref "U$10") (pin "40") (pinfunction "P15[2](KHZ_XTAL:XO,GPIO)_40") (pintype "bidirectional"))
    )
    (net (code "67") (name "Net-(U$10-P15[3](KHZ_XTAL:XI,GPIO))") (class "Default")
      (node (ref "R25") (pin "2") (pinfunction "2_2") (pintype "passive"))
      (node (ref "R30") (pin "2") (pinfunction "2_2") (pintype "passive"))
      (node (ref "U$10") (pin "41") (pinfunction "P15[3](KHZ_XTAL:XI,GPIO)_41") (pintype "bidirectional"))
    )
    (net (code "68") (name "Net-(U$10-VCCA_3)") (class "Default")
      (node (ref "C21") (pin "1") (pinfunction "1_1") (pintype "passive"))
      (node (ref "U$10") (pin "42") (pinfunction "VCCA_3_42") (pintype "bidirectional"))
    )
    (net (code "69") (name "Net-(U$11-HB)") (class "Default")
      (node (ref "C8") (pin "2") (pinfunction "2_2") (pintype "passive"))
      (node (ref "U$11") (pin "8") (pinfunction "HB_8") (pintype "bidirectional"))
    )
    (net (code "70") (name "Net-(U$11-HO)") (class "Default")
      (node (ref "R12") (pin "1") (pinfunction "1_1") (pintype "passive"))
      (node (ref "U$11") (pin "7") (pinfunction "HO_7") (pintype "bidirectional"))
    )
    (net (code "71") (name "Net-(U$11-LO)") (class "Default")
      (node (ref "R13") (pin "1") (pinfunction "1_1") (pintype "passive"))
      (node (ref "U$11") (pin "5") (pinfunction "LO_5") (pintype "bidirectional"))
    )
    (net (code "72") (name "Net-(U$14A-RS-)") (class "Default")
      (node (ref "R7") (pin "1") (pinfunction "1_1") (pintype "passive"))
      (node (ref "U$14") (pin "6") (pinfunction "RS-_6") (pintype "bidirectional"))
      (node (ref "U$17") (pin "5") (pinfunction "D_5") (pintype "bidirectional"))
      (node (ref "U$17") (pin "5678") (pinfunction "D_5678") (pintype "bidirectional"))
      (node (ref "U$17") (pin "6") (pinfunction "D_6") (pintype "bidirectional"))
      (node (ref "U$17") (pin "7") (pinfunction "D_7") (pintype "bidirectional"))
      (node (ref "U$17") (pin "8") (pinfunction "D_8") (pintype "bidirectional"))
    )
    (net (code "73") (name "Net-(U$15A-RS-)") (class "Default")
      (node (ref "R6") (pin "1") (pinfunction "1_1") (pintype "passive"))
      (node (ref "U$15") (pin "6") (pinfunction "RS-_6") (pintype "bidirectional"))
      (node (ref "U$18") (pin "5") (pinfunction "D_5") (pintype "bidirectional"))
      (node (ref "U$18") (pin "5678") (pinfunction "D_5678") (pintype "bidirectional"))
      (node (ref "U$18") (pin "6") (pinfunction "D_6") (pintype "bidirectional"))
      (node (ref "U$18") (pin "7") (pinfunction "D_7") (pintype "bidirectional"))
      (node (ref "U$18") (pin "8") (pinfunction "D_8") (pintype "bidirectional"))
    )
    (net (code "74") (name "Net-(U$16-G)") (class "Default")
      (node (ref "R9") (pin "2") (pinfunction "2_2") (pintype "passive"))
      (node (ref "U$16") (pin "4") (pinfunction "G_4") (pintype "bidirectional"))
    )
    (net (code "75") (name "Net-(U$17-G)") (class "Default")
      (node (ref "R1") (pin "2") (pinfunction "2_2") (pintype "passive"))
      (node (ref "U$17") (pin "4") (pinfunction "G_4") (pintype "bidirectional"))
    )
    (net (code "76") (name "Net-(U$18-G)") (class "Default")
      (node (ref "R10") (pin "2") (pinfunction "2_2") (pintype "passive"))
      (node (ref "U$18") (pin "4") (pinfunction "G_4") (pintype "bidirectional"))
    )
    (net (code "77") (name "Net-(U$19-G)") (class "Default")
      (node (ref "R11") (pin "2") (pinfunction "2_2") (pintype "passive"))
      (node (ref "U$19") (pin "4") (pinfunction "G_4") (pintype "bidirectional"))
    )
    (net (code "78") (name "Net-(U$20-G)") (class "Default")
      (node (ref "R12") (pin "2") (pinfunction "2_2") (pintype "passive"))
      (node (ref "U$20") (pin "4") (pinfunction "G_4") (pintype "bidirectional"))
    )
    (net (code "79") (name "Net-(U$21-G)") (class "Default")
      (node (ref "R13") (pin "2") (pinfunction "2_2") (pintype "passive"))
      (node (ref "U$21") (pin "4") (pinfunction "G_4") (pintype "bidirectional"))
    )
    (net (code "80") (name "Net-(U$22A-RS-)") (class "Default")
      (node (ref "R5") (pin "1") (pinfunction "1_1") (pintype "passive"))
      (node (ref "U$20") (pin "5") (pinfunction "D_5") (pintype "bidirectional"))
      (node (ref "U$20") (pin "5678") (pinfunction "D_5678") (pintype "bidirectional"))
      (node (ref "U$20") (pin "6") (pinfunction "D_6") (pintype "bidirectional"))
      (node (ref "U$20") (pin "7") (pinfunction "D_7") (pintype "bidirectional"))
      (node (ref "U$20") (pin "8") (pinfunction "D_8") (pintype "bidirectional"))
      (node (ref "U$22") (pin "6") (pinfunction "RS-_6") (pintype "bidirectional"))
    )
    (net (code "81") (name "U") (class "Default")
      (node (ref "C6") (pin "1") (pinfunction "1_1") (pintype "passive"))
      (node (ref "R14") (pin "2") (pinfunction "2_2") (pintype "passive"))
      (node (ref "U$16") (pin "5") (pinfunction "D_5") (pintype "bidirectional"))
      (node (ref "U$16") (pin "5678") (pinfunction "D_5678") (pintype "bidirectional"))
      (node (ref "U$16") (pin "6") (pinfunction "D_6") (pintype "bidirectional"))
      (node (ref "U$16") (pin "7") (pinfunction "D_7") (pintype "bidirectional"))
      (node (ref "U$16") (pin "8") (pinfunction "D_8") (pintype "bidirectional"))
      (node (ref "U$17") (pin "1") (pinfunction "S_1") (pintype "bidirectional"))
      (node (ref "U$17") (pin "123") (pinfunction "S_123") (pintype "bidirectional"))
      (node (ref "U$17") (pin "2") (pinfunction "S_2") (pintype "bidirectional"))
      (node (ref "U$17") (pin "3") (pinfunction "S_3") (pintype "bidirectional"))
      (node (ref "U$2") (pin "1") (pinfunction "1_1") (pintype "bidirectional"))
      (node (ref "U$8") (pin "9") (pinfunction "HS_9") (pintype "bidirectional"))
    )
    (net (code "82") (name "U_ADC") (class "Default")
      (node (ref "R14") (pin "1") (pinfunction "1_1") (pintype "passive"))
      (node (ref "R15") (pin "2") (pinfunction "2_2") (pintype "passive"))
      (node (ref "U$10") (pin "49") (pinfunction "P0[1](GPIO)_49") (pintype "bidirectional"))
    )
    (net (code "83") (name "U_I_ADC") (class "Default")
      (node (ref "U$10") (pin "50") (pinfunction "P0[2](GPIO)_50") (pintype "bidirectional"))
      (node (ref "U$14") (pin "3") (pinfunction "OUT_3") (pintype "bidirectional"))
    )
    (net (code "84") (name "V") (class "Default")
      (node (ref "C7") (pin "1") (pinfunction "1_1") (pintype "passive"))
      (node (ref "R16") (pin "2") (pinfunction "2_2") (pintype "passive"))
      (node (ref "U$18") (pin "1") (pinfunction "S_1") (pintype "bidirectional"))
      (node (ref "U$18") (pin "123") (pinfunction "S_123") (pintype "bidirectional"))
      (node (ref "U$18") (pin "2") (pinfunction "S_2") (pintype "bidirectional"))
      (node (ref "U$18") (pin "3") (pinfunction "S_3") (pintype "bidirectional"))
      (node (ref "U$19") (pin "5") (pinfunction "D_5") (pintype "bidirectional"))
      (node (ref "U$19") (pin "5678") (pinfunction "D_5678") (pintype "bidirectional"))
      (node (ref "U$19") (pin "6") (pinfunction "D_6") (pintype "bidirectional"))
      (node (ref "U$19") (pin "7") (pinfunction "D_7") (pintype "bidirectional"))
      (node (ref "U$19") (pin "8") (pinfunction "D_8") (pintype "bidirectional"))
      (node (ref "U$2") (pin "2") (pinfunction "2_2") (pintype "bidirectional"))
      (node (ref "U$9") (pin "6") (pinfunction "HS_6") (pintype "bidirectional"))
    )
    (net (code "85") (name "VCC_1") (class "Default")
      (node (ref "C20") (pin "1") (pinfunction "1_1") (pintype "passive"))
      (node (ref "U$10") (pin "26") (pinfunction "VCCD_2_26") (pintype "bidirectional"))
      (node (ref "U$10") (pin "57") (pinfunction "VCCD_4_57") (pintype "bidirectional"))
    )
    (net (code "86") (name "VDD") (class "Default")
      (node (ref "C1") (pin "1") (pinfunction "1_1") (pintype "passive"))
      (node (ref "C2") (pin "1") (pinfunction "1_1") (pintype "passive"))
      (node (ref "C3") (pin "1") (pinfunction "1_1") (pintype "passive"))
      (node (ref "C38") (pin "+") (pinfunction "+_+") (pintype "passive"))
      (node (ref "C39") (pin "+") (pinfunction "+_+") (pintype "passive"))
      (node (ref "C4") (pin "1") (pinfunction "1_1") (pintype "passive"))
      (node (ref "D1") (pin "A") (pinfunction "A_A") (pintype "passive"))
      (node (ref "D2") (pin "A") (pinfunction "A_A") (pintype "passive"))
      (node (ref "D3") (pin "A") (pinfunction "A_A") (pintype "passive"))
      (node (ref "R22") (pin "A2") (pinfunction "2_A2") (pintype "passive"))
      (node (ref "R22") (pin "B2") (pinfunction "2_B2") (pintype "passive"))
      (node (ref "R28") (pin "2") (pinfunction "2_2") (pintype "passive"))
      (node (ref "R5") (pin "2") (pinfunction "2_2") (pintype "passive"))
      (node (ref "R6") (pin "2") (pinfunction "2_2") (pintype "passive"))
      (node (ref "R7") (pin "2") (pinfunction "2_2") (pintype "passive"))
      (node (ref "U$14") (pin "5") (pinfunction "RS+_5") (pintype "bidirectional"))
      (node (ref "U$15") (pin "5") (pinfunction "RS+_5") (pintype "bidirectional"))
      (node (ref "U$22") (pin "5") (pinfunction "RS+_5") (pintype "bidirectional"))
      (node (ref "U$3") (pin "2") (pinfunction "1_2") (pintype "bidirectional"))
    )
    (net (code "87") (name "VDDEN") (class "Default")
      (node (ref "R8") (pin "2") (pinfunction "2_2") (pintype "passive"))
      (node (ref "U$10") (pin "54") (pinfunction "P0[5](GPIO)_54") (pintype "bidirectional"))
    )
    (net (code "88") (name "VDD_ADC") (class "Default")
      (node (ref "R27") (pin "2") (pinfunction "2_2") (pintype "passive"))
      (node (ref "R28") (pin "1") (pinfunction "1_1") (pintype "passive"))
      (node (ref "U$10") (pin "48") (pinfunction "P0[0](GPIO)_48") (pintype "bidirectional"))
    )
    (net (code "89") (name "V_ADC") (class "Default")
      (node (ref "R16") (pin "1") (pinfunction "1_1") (pintype "passive"))
      (node (ref "R17") (pin "2") (pinfunction "2_2") (pintype "passive"))
      (node (ref "U$10") (pin "51") (pinfunction "P0[3](GPIO)_51") (pintype "bidirectional"))
    )
    (net (code "90") (name "V_I_ADC") (class "Default")
      (node (ref "U$10") (pin "53") (pinfunction "P0[4](GPIO)_53") (pintype "bidirectional"))
      (node (ref "U$15") (pin "3") (pinfunction "OUT_3") (pintype "bidirectional"))
    )
    (net (code "91") (name "W") (class "Default")
      (node (ref "C8") (pin "1") (pinfunction "1_1") (pintype "passive"))
      (node (ref "R18") (pin "2") (pinfunction "2_2") (pintype "passive"))
      (node (ref "U$11") (pin "6") (pinfunction "HS_6") (pintype "bidirectional"))
      (node (ref "U$2") (pin "3") (pinfunction "3_3") (pintype "bidirectional"))
      (node (ref "U$20") (pin "1") (pinfunction "S_1") (pintype "bidirectional"))
      (node (ref "U$20") (pin "123") (pinfunction "S_123") (pintype "bidirectional"))
      (node (ref "U$20") (pin "2") (pinfunction "S_2") (pintype "bidirectional"))
      (node (ref "U$20") (pin "3") (pinfunction "S_3") (pintype "bidirectional"))
      (node (ref "U$21") (pin "5") (pinfunction "D_5") (pintype "bidirectional"))
      (node (ref "U$21") (pin "5678") (pinfunction "D_5678") (pintype "bidirectional"))
      (node (ref "U$21") (pin "6") (pinfunction "D_6") (pintype "bidirectional"))
      (node (ref "U$21") (pin "7") (pinfunction "D_7") (pintype "bidirectional"))
      (node (ref "U$21") (pin "8") (pinfunction "D_8") (pintype "bidirectional"))
    )
    (net (code "92") (name "W_ADC") (class "Default")
      (node (ref "R18") (pin "1") (pinfunction "1_1") (pintype "passive"))
      (node (ref "R19") (pin "2") (pinfunction "2_2") (pintype "passive"))
      (node (ref "U$10") (pin "1") (pinfunction "P2[6](GPIO)_1") (pintype "bidirectional"))
    )
    (net (code "93") (name "W_I_ADC") (class "Default")
      (node (ref "U$10") (pin "2") (pinfunction "P2[7](GPIO)_2") (pintype "bidirectional"))
      (node (ref "U$22") (pin "3") (pinfunction "OUT_3") (pintype "bidirectional"))
    )
    (net (code "94") (name "unconnected-(H1-MOUNT-PadB3,0)") (class "Default")
      (node (ref "H1") (pin "B3,0") (pinfunction "MOUNT_B3,0") (pintype "passive"))
    )
    (net (code "95") (name "unconnected-(H2-MOUNT-PadB3,0)") (class "Default")
      (node (ref "H2") (pin "B3,0") (pinfunction "MOUNT_B3,0") (pintype "passive"))
    )
    (net (code "96") (name "unconnected-(H3-MOUNT-PadB3,0)") (class "Default")
      (node (ref "H3") (pin "B3,0") (pinfunction "MOUNT_B3,0") (pintype "passive"))
    )
    (net (code "97") (name "unconnected-(H4-MOUNT-PadB3,0)") (class "Default")
      (node (ref "H4") (pin "B3,0") (pinfunction "MOUNT_B3,0") (pintype "passive"))
    )
    (net (code "98") (name "unconnected-(PMW-Pad2)") (class "Default")
      (node (ref "PMW") (pin "2") (pinfunction "2_2") (pintype "passive"))
    )
    (net (code "99") (name "unconnected-(U$5-RT{slash}SYNC-Pad6)") (class "Default")
      (node (ref "U$5") (pin "6") (pinfunction "RT/SYNC_6") (pintype "bidirectional"))
    )
    (net (code "100") (name "unconnected-(U$5-~{RESET}-Pad3)") (class "Default")
      (node (ref "U$5") (pin "3") (pinfunction "~{RESET}_3") (pintype "bidirectional"))
    )
    (net (code "101") (name "unconnected-(U$8-VCC_OUT-Pad3)") (class "Default")
      (node (ref "U$8") (pin "3") (pinfunction "VCC_OUT_3") (pintype "bidirectional"))
    )
    (net (code "102") (name "unconnected-(U$8-VCEN-Pad2)") (class "Default")
      (node (ref "U$8") (pin "2") (pinfunction "VCEN_2") (pintype "bidirectional"))
    )
    (net (code "103") (name "unconnected-(U$10-IND-Pad6)") (class "Default")
      (node (ref "U$10") (pin "6") (pinfunction "IND_6") (pintype "bidirectional"))
    )
    (net (code "104") (name "unconnected-(U$10-P0[6](IDAC0,GPIO)-Pad55)") (class "Default")
      (node (ref "U$10") (pin "55") (pinfunction "P0[6](IDAC0,GPIO)_55") (pintype "bidirectional"))
    )
    (net (code "105") (name "unconnected-(U$10-P0[7](IDAC2,GPIO)-Pad56)") (class "Default")
      (node (ref "U$10") (pin "56") (pinfunction "P0[7](IDAC2,GPIO)_56") (pintype "bidirectional"))
    )
    (net (code "106") (name "unconnected-(U$10-P1[2](~{XRES,GPIO})-Pad13)") (class "Default")
      (node (ref "U$10") (pin "13") (pinfunction "P1[2](~{XRES,GPIO})_13") (pintype "bidirectional"))
    )
    (net (code "107") (name "unconnected-(U$10-P1[4](TDI,GPIO)-Pad15)") (class "Default")
      (node (ref "U$10") (pin "15") (pinfunction "P1[4](TDI,GPIO)_15") (pintype "bidirectional"))
    )
    (net (code "108") (name "unconnected-(U$10-P1[5](NTRST,GPIO)-Pad16)") (class "Default")
      (node (ref "U$10") (pin "16") (pinfunction "P1[5](NTRST,GPIO)_16") (pintype "bidirectional"))
    )
    (net (code "109") (name "unconnected-(U$10-P2[4](GPIO)-Pad66)") (class "Default")
      (node (ref "U$10") (pin "66") (pinfunction "P2[4](GPIO)_66") (pintype "bidirectional"))
    )
    (net (code "110") (name "unconnected-(U$10-P2[5](GPIO)-Pad68)") (class "Default")
      (node (ref "U$10") (pin "68") (pinfunction "P2[5](GPIO)_68") (pintype "bidirectional"))
    )
    (net (code "111") (name "unconnected-(U$10-P3[0](GPIO)-Pad29)") (class "Default")
      (node (ref "U$10") (pin "29") (pinfunction "P3[0](GPIO)_29") (pintype "bidirectional"))
    )
    (net (code "112") (name "unconnected-(U$10-P3[1](GPIO)-Pad30)") (class "Default")
      (node (ref "U$10") (pin "30") (pinfunction "P3[1](GPIO)_30") (pintype "bidirectional"))
    )
    (net (code "113") (name "unconnected-(U$10-P12[6](SIO)-Pad20)") (class "Default")
      (node (ref "U$10") (pin "20") (pinfunction "P12[6](SIO)_20") (pintype "bidirectional"))
    )
    (net (code "114") (name "unconnected-(U$10-P12[7](SIO)-Pad21)") (class "Default")
      (node (ref "U$10") (pin "21") (pinfunction "P12[7](SIO)_21") (pintype "bidirectional"))
    )
    (net (code "115") (name "unconnected-(U$10-P15[6](USBIO,D+,SWDIO)-Pad22)") (class "Default")
      (node (ref "U$10") (pin "22") (pinfunction "P15[6](USBIO,D+,SWDIO)_22") (pintype "bidirectional"))
    )
    (net (code "116") (name "unconnected-(U$10-P15[7](USBIO,D-,SWDCK)-Pad23)") (class "Default")
      (node (ref "U$10") (pin "23") (pinfunction "P15[7](USBIO,D-,SWDCK)_23") (pintype "bidirectional"))
    )
    (net (code "117") (name "unconnected-(UART-Pad2)") (class "Default")
      (node (ref "UART") (pin "2") (pinfunction "2_2") (pintype "passive"))
    )
  )
)
